# 4GModule-EC25.net
KiCad netlist of a schematic drawn in Altium Designer
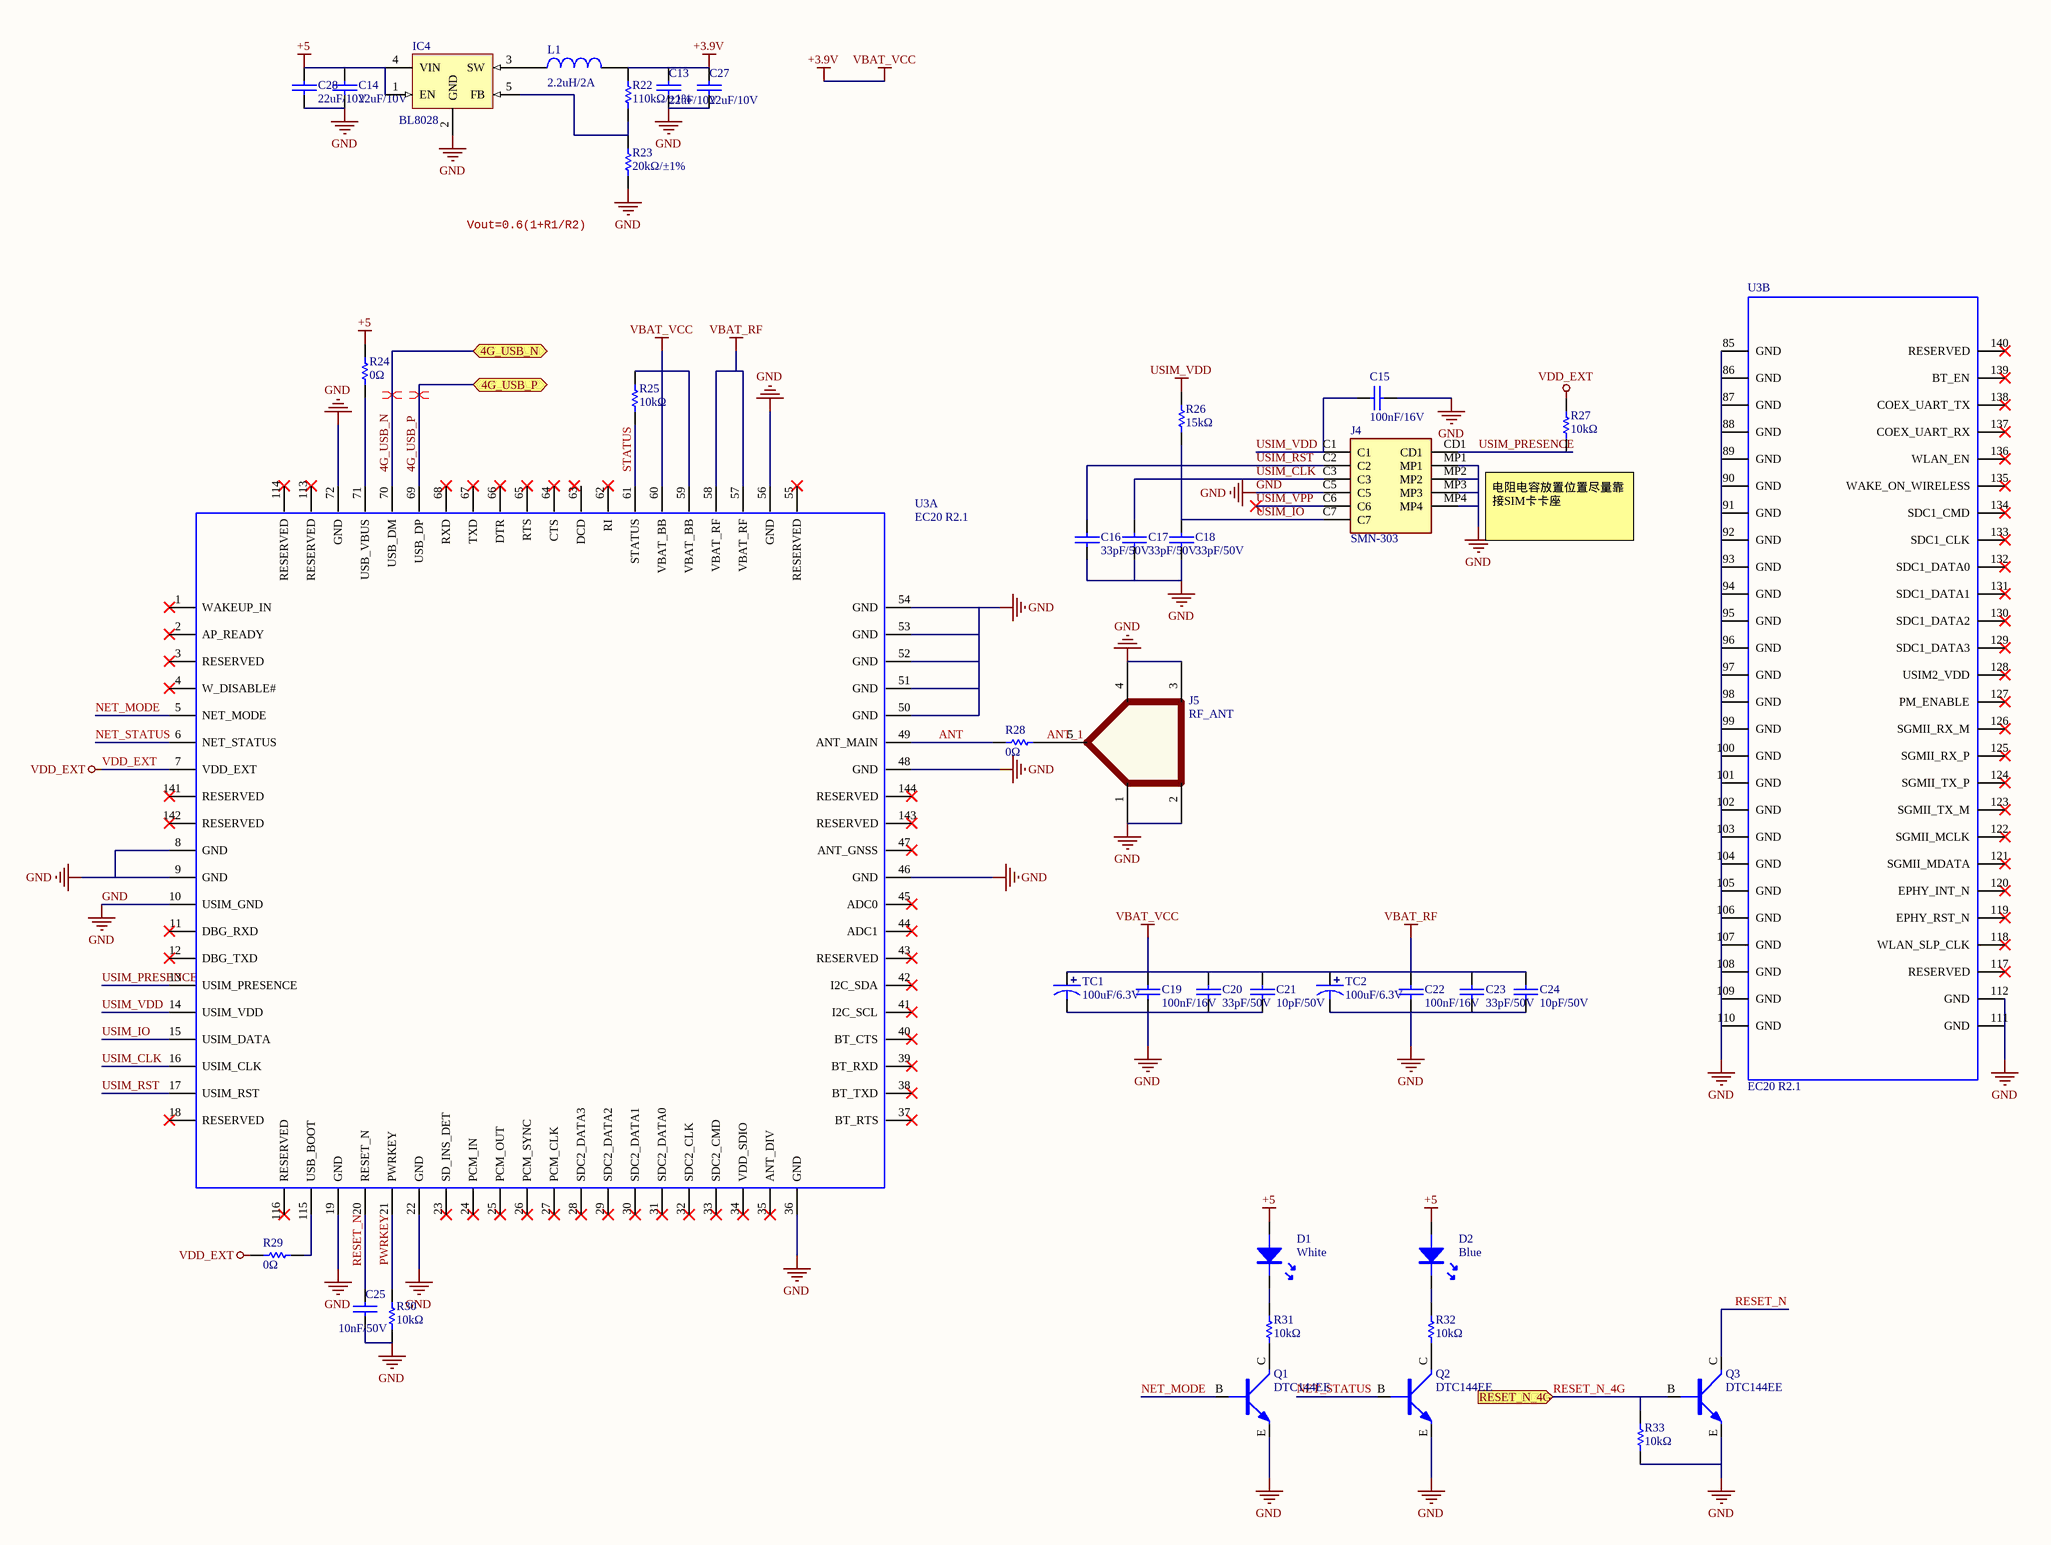
[diagram p0: 4GModule-EC25.SchDoc]

(export (version "E")
  (design (tool "Eeschema 10.0.6"))
  (components
    (comp (ref "C13")
      (value "22uF/10V")
      (footprint "C_0603")
      (description "贴片电容")
      (libsource (lib "IntLib-Passive") (part "Cap_MLCC"))
    )
    (comp (ref "C14")
      (value "22uF/10V")
      (footprint "C_0603")
      (description "贴片电容")
      (libsource (lib "IntLib-Passive") (part "Cap_MLCC"))
    )
    (comp (ref "C15")
      (value "100nF/16V")
      (footprint "C_0402")
      (description "贴片电容")
      (libsource (lib "IntLib-Passive") (part "Cap_MLCC"))
    )
    (comp (ref "C16")
      (value "33pF/50V")
      (footprint "C_0402")
      (description "贴片电容")
      (libsource (lib "IntLib-Passive") (part "Cap_MLCC"))
    )
    (comp (ref "C17")
      (value "33pF/50V")
      (footprint "C_0402")
      (description "贴片电容")
      (libsource (lib "IntLib-Passive") (part "Cap_MLCC"))
    )
    (comp (ref "C18")
      (value "33pF/50V")
      (footprint "C_0402")
      (description "贴片电容")
      (libsource (lib "IntLib-Passive") (part "Cap_MLCC"))
    )
    (comp (ref "C19")
      (value "100nF/16V")
      (footprint "C_0402")
      (description "贴片电容")
      (libsource (lib "IntLib-Passive") (part "Cap_MLCC"))
    )
    (comp (ref "C20")
      (value "33pF/50V")
      (footprint "C_0402")
      (description "贴片电容")
      (libsource (lib "IntLib-Passive") (part "Cap_MLCC"))
    )
    (comp (ref "C21")
      (value "10pF/50V")
      (footprint "C_0402")
      (description "贴片电容")
      (libsource (lib "IntLib-Passive") (part "Cap_MLCC"))
    )
    (comp (ref "C22")
      (value "100nF/16V")
      (footprint "C_0402")
      (description "贴片电容")
      (libsource (lib "IntLib-Passive") (part "Cap_MLCC"))
    )
    (comp (ref "C23")
      (value "33pF/50V")
      (footprint "C_0402")
      (description "贴片电容")
      (libsource (lib "IntLib-Passive") (part "Cap_MLCC"))
    )
    (comp (ref "C24")
      (value "10pF/50V")
      (footprint "C_0402")
      (description "贴片电容")
      (libsource (lib "IntLib-Passive") (part "Cap_MLCC"))
    )
    (comp (ref "C25")
      (value "10nF/50V")
      (footprint "C_0402")
      (description "贴片电容")
      (libsource (lib "IntLib-Passive") (part "Cap_MLCC"))
    )
    (comp (ref "C27")
      (value "22uF/10V")
      (footprint "IntLib-Passive:C_0603")
      (description "贴片电容")
      (libsource (lib "IntLib-Passive") (part "Cap_MLCC"))
    )
    (comp (ref "C28")
      (value "22uF/10V")
      (footprint "IntLib-Passive:C_0603")
      (description "贴片电容")
      (libsource (lib "IntLib-Passive") (part "Cap_MLCC"))
    )
    (comp (ref "D1")
      (value "White")
      (footprint "LED-0603-W")
      (description "贴片LED")
      (libsource (lib "IntLib-Active") (part "LED_SMD"))
    )
    (comp (ref "D2")
      (value "Blue")
      (footprint "LED-0603-B")
      (description "贴片LED")
      (libsource (lib "IntLib-Active") (part "LED_SMD"))
    )
    (comp (ref "IC4")
      (value "BL8028")
      (footprint "SOT23-5")
      (description "DC-DC 芯片")
      (libsource (lib "IntLib-IC") (part "BL8028"))
    )
    (comp (ref "J4")
      (value "SMN-303")
      (footprint "SimCard_SMN-303")
      (description "NANO SIM卡座")
      (libsource (lib "IntLib-Connector") (part "SimCard_Nano"))
    )
    (comp (ref "J5")
      (value "RF_ANT")
      (footprint "RF_MCX")
      (description "RF 天线座")
      (libsource (lib "IntLib-Connector") (part "RF_ANT"))
    )
    (comp (ref "L1")
      (value "2.2uH/2A")
      (footprint "IntLib-Passive:L_1008")
      (description "小功率贴片电感")
      (libsource (lib "Passive-Ind") (part "Ind_SMD"))
    )
    (comp (ref "Q1")
      (value "DTC144EE")
      (footprint "IntLib-Active:SOT-523")
      (description "NPN三极管")
      (libsource (lib "Active-BJT") (part "BJT_NPN"))
    )
    (comp (ref "Q2")
      (value "DTC144EE")
      (footprint "IntLib-Active:SOT-523")
      (description "NPN三极管")
      (libsource (lib "Active-BJT") (part "BJT_NPN"))
    )
    (comp (ref "Q3")
      (value "DTC144EE")
      (footprint "IntLib-Active:SOT-523")
      (description "NPN三极管")
      (libsource (lib "Active-BJT") (part "BJT_NPN"))
    )
    (comp (ref "R22")
      (value "110kΩ/±1%")
      (footprint "R_0402")
      (description "贴片电阻")
      (libsource (lib "IntLib-Passive") (part "Res_SMD"))
    )
    (comp (ref "R23")
      (value "20kΩ/±1%")
      (footprint "R_0402")
      (description "贴片电阻")
      (libsource (lib "IntLib-Passive") (part "Res_SMD"))
    )
    (comp (ref "R24")
      (value "0Ω")
      (footprint "R_0402")
      (description "贴片电阻")
      (libsource (lib "IntLib-Passive") (part "Res_SMD"))
    )
    (comp (ref "R25")
      (value "10kΩ")
      (footprint "R_0402")
      (description "贴片电阻")
      (libsource (lib "IntLib-Passive") (part "Res_SMD"))
    )
    (comp (ref "R26")
      (value "15kΩ")
      (footprint "R_0402")
      (description "贴片电阻")
      (libsource (lib "IntLib-Passive") (part "Res_SMD"))
    )
    (comp (ref "R27")
      (value "10kΩ")
      (footprint "R_0402")
      (description "贴片电阻")
      (libsource (lib "IntLib-Passive") (part "Res_SMD"))
    )
    (comp (ref "R28")
      (value "0Ω")
      (footprint "R_0402")
      (description "贴片电阻")
      (libsource (lib "IntLib-Passive") (part "Res_SMD"))
    )
    (comp (ref "R29")
      (value "0Ω")
      (footprint "R_0402")
      (description "贴片电阻")
      (libsource (lib "IntLib-Passive") (part "Res_SMD"))
    )
    (comp (ref "R30")
      (value "10kΩ")
      (footprint "R_0402")
      (description "贴片电阻")
      (libsource (lib "IntLib-Passive") (part "Res_SMD"))
    )
    (comp (ref "R31")
      (value "10kΩ")
      (footprint "R_0402")
      (description "贴片电阻")
      (libsource (lib "IntLib-Passive") (part "Res_SMD"))
    )
    (comp (ref "R32")
      (value "10kΩ")
      (footprint "R_0402")
      (description "贴片电阻")
      (libsource (lib "IntLib-Passive") (part "Res_SMD"))
    )
    (comp (ref "R33")
      (value "10kΩ")
      (footprint "R_0402")
      (description "贴片电阻")
      (libsource (lib "IntLib-Passive") (part "Res_SMD"))
    )
    (comp (ref "TC1")
      (value "100uF/6.3V")
      (footprint "TAJ-B/3528")
      (description "钽电容")
      (libsource (lib "IntLib-Passive") (part "Cap_TAN"))
    )
    (comp (ref "TC2")
      (value "100uF/6.3V")
      (footprint "TAJ-B/3528")
      (description "钽电容")
      (libsource (lib "IntLib-Passive") (part "Cap_TAN"))
    )
    (comp (ref "U3")
      (value "EC20 R2.1")
      (footprint "IntLib-Module:LCC-144_29.0X32.0X1.3P")
      (description "EC20邮票孔模组")
      (libsource (lib "Module-RF") (part "Module_EC20-R2.1"))
    )
  )
  (nets
    (net (code "1") (name "+3.9V") (class "Default")
      (node (ref "C13") (pin "2") (pinfunction "2_2") (pintype "passive"))
      (node (ref "C19") (pin "2") (pinfunction "2_2") (pintype "passive"))
      (node (ref "C20") (pin "2") (pinfunction "2_2") (pintype "passive"))
      (node (ref "C21") (pin "2") (pinfunction "2_2") (pintype "passive"))
      (node (ref "C22") (pin "2") (pinfunction "2_2") (pintype "passive"))
      (node (ref "C23") (pin "2") (pinfunction "2_2") (pintype "passive"))
      (node (ref "C24") (pin "2") (pinfunction "2_2") (pintype "passive"))
      (node (ref "C27") (pin "2") (pinfunction "2_2") (pintype "passive"))
      (node (ref "L1") (pin "2") (pinfunction "2_2") (pintype "passive"))
      (node (ref "R22") (pin "2") (pinfunction "2_2") (pintype "passive"))
      (node (ref "R25") (pin "2") (pinfunction "2_2") (pintype "passive"))
      (node (ref "TC1") (pin "1") (pinfunction "1_1") (pintype "passive"))
      (node (ref "TC2") (pin "1") (pinfunction "1_1") (pintype "passive"))
      (node (ref "U3") (pin "57") (pinfunction "VBAT_RF_57") (pintype "passive"))
      (node (ref "U3") (pin "58") (pinfunction "VBAT_RF_58") (pintype "passive"))
      (node (ref "U3") (pin "59") (pinfunction "VBAT_BB_59") (pintype "passive"))
      (node (ref "U3") (pin "60") (pinfunction "VBAT_BB_60") (pintype "passive"))
    )
    (net (code "2") (name "+5") (class "Default")
      (node (ref "C14") (pin "2") (pinfunction "2_2") (pintype "passive"))
      (node (ref "C28") (pin "2") (pinfunction "2_2") (pintype "passive"))
      (node (ref "D1") (pin "A") (pinfunction "A_A") (pintype "passive"))
      (node (ref "D2") (pin "A") (pinfunction "A_A") (pintype "passive"))
      (node (ref "IC4") (pin "1") (pinfunction "EN_1") (pintype "input"))
      (node (ref "IC4") (pin "4") (pinfunction "VIN_4") (pintype "power_in"))
      (node (ref "R24") (pin "2") (pinfunction "2_2") (pintype "passive"))
    )
    (net (code "3") (name "/4G_USB_N") (class "Default")
      (node (ref "U3") (pin "70") (pinfunction "USB_DM_70") (pintype "passive"))
    )
    (net (code "4") (name "/4G_USB_P") (class "Default")
      (node (ref "U3") (pin "69") (pinfunction "USB_DP_69") (pintype "passive"))
    )
    (net (code "5") (name "/ANT") (class "Default")
      (node (ref "R28") (pin "1") (pinfunction "1_1") (pintype "passive"))
      (node (ref "U3") (pin "49") (pinfunction "ANT_MAIN_49") (pintype "passive"))
    )
    (net (code "6") (name "/ANT_1") (class "Default")
      (node (ref "J5") (pin "5") (pinfunction "5_5") (pintype "passive"))
      (node (ref "R28") (pin "2") (pinfunction "2_2") (pintype "passive"))
    )
    (net (code "7") (name "/NET_MODE") (class "Default")
      (node (ref "Q1") (pin "B") (pinfunction "B_B") (pintype "passive"))
      (node (ref "U3") (pin "5") (pinfunction "NET_MODE_5") (pintype "passive"))
    )
    (net (code "8") (name "/NET_STATUS") (class "Default")
      (node (ref "Q2") (pin "B") (pinfunction "B_B") (pintype "passive"))
      (node (ref "U3") (pin "6") (pinfunction "NET_STATUS_6") (pintype "passive"))
    )
    (net (code "9") (name "/PWRKEY") (class "Default")
      (node (ref "R30") (pin "2") (pinfunction "2_2") (pintype "passive"))
      (node (ref "U3") (pin "21") (pinfunction "PWRKEY_21") (pintype "passive"))
    )
    (net (code "10") (name "/RESET_N") (class "Default")
      (node (ref "C25") (pin "2") (pinfunction "2_2") (pintype "passive"))
      (node (ref "Q3") (pin "C") (pinfunction "C_C") (pintype "passive"))
      (node (ref "U3") (pin "20") (pinfunction "RESET_N_20") (pintype "passive"))
    )
    (net (code "11") (name "/RESET_N_4G") (class "Default")
      (node (ref "Q3") (pin "B") (pinfunction "B_B") (pintype "passive"))
      (node (ref "R33") (pin "2") (pinfunction "2_2") (pintype "passive"))
    )
    (net (code "12") (name "/STATUS") (class "Default")
      (node (ref "R25") (pin "1") (pinfunction "1_1") (pintype "passive"))
      (node (ref "U3") (pin "61") (pinfunction "STATUS_61") (pintype "passive"))
    )
    (net (code "13") (name "/USIM_CLK") (class "Default")
      (node (ref "C17") (pin "2") (pinfunction "2_2") (pintype "passive"))
      (node (ref "J4") (pin "C3") (pinfunction "C3_C3") (pintype "passive"))
      (node (ref "U3") (pin "16") (pinfunction "USIM_CLK_16") (pintype "passive"))
    )
    (net (code "14") (name "/USIM_IO") (class "Default")
      (node (ref "C18") (pin "2") (pinfunction "2_2") (pintype "passive"))
      (node (ref "J4") (pin "C7") (pinfunction "C7_C7") (pintype "passive"))
      (node (ref "R26") (pin "1") (pinfunction "1_1") (pintype "passive"))
      (node (ref "U3") (pin "15") (pinfunction "USIM_DATA_15") (pintype "passive"))
    )
    (net (code "15") (name "/USIM_PRESENCE") (class "Default")
      (node (ref "J4") (pin "CD1") (pinfunction "CD1_CD1") (pintype "passive"))
      (node (ref "R27") (pin "1") (pinfunction "1_1") (pintype "passive"))
      (node (ref "U3") (pin "13") (pinfunction "USIM_PRESENCE_13") (pintype "passive"))
    )
    (net (code "16") (name "/USIM_RST") (class "Default")
      (node (ref "C16") (pin "2") (pinfunction "2_2") (pintype "passive"))
      (node (ref "J4") (pin "C2") (pinfunction "C2_C2") (pintype "passive"))
      (node (ref "U3") (pin "17") (pinfunction "USIM_RST_17") (pintype "passive"))
    )
    (net (code "17") (name "/USIM_VPP") (class "Default")
      (node (ref "J4") (pin "C6") (pinfunction "C6_C6") (pintype "passive+no_connect"))
    )
    (net (code "18") (name "GND") (class "Default")
      (node (ref "C13") (pin "1") (pinfunction "1_1") (pintype "passive"))
      (node (ref "C14") (pin "1") (pinfunction "1_1") (pintype "passive"))
      (node (ref "C15") (pin "1") (pinfunction "1_1") (pintype "passive"))
      (node (ref "C16") (pin "1") (pinfunction "1_1") (pintype "passive"))
      (node (ref "C17") (pin "1") (pinfunction "1_1") (pintype "passive"))
      (node (ref "C18") (pin "1") (pinfunction "1_1") (pintype "passive"))
      (node (ref "C19") (pin "1") (pinfunction "1_1") (pintype "passive"))
      (node (ref "C20") (pin "1") (pinfunction "1_1") (pintype "passive"))
      (node (ref "C21") (pin "1") (pinfunction "1_1") (pintype "passive"))
      (node (ref "C22") (pin "1") (pinfunction "1_1") (pintype "passive"))
      (node (ref "C23") (pin "1") (pinfunction "1_1") (pintype "passive"))
      (node (ref "C24") (pin "1") (pinfunction "1_1") (pintype "passive"))
      (node (ref "C25") (pin "1") (pinfunction "1_1") (pintype "passive"))
      (node (ref "C27") (pin "1") (pinfunction "1_1") (pintype "passive"))
      (node (ref "C28") (pin "1") (pinfunction "1_1") (pintype "passive"))
      (node (ref "IC4") (pin "2") (pinfunction "GND_2") (pintype "power_in"))
      (node (ref "J4") (pin "C5") (pinfunction "C5_C5") (pintype "passive"))
      (node (ref "J4") (pin "MP1") (pinfunction "MP1_MP1") (pintype "passive"))
      (node (ref "J4") (pin "MP2") (pinfunction "MP2_MP2") (pintype "passive"))
      (node (ref "J4") (pin "MP3") (pinfunction "MP3_MP3") (pintype "passive"))
      (node (ref "J4") (pin "MP4") (pinfunction "MP4_MP4") (pintype "passive"))
      (node (ref "J5") (pin "1") (pinfunction "1_1") (pintype "passive"))
      (node (ref "J5") (pin "2") (pinfunction "2_2") (pintype "passive"))
      (node (ref "J5") (pin "3") (pinfunction "3_3") (pintype "passive"))
      (node (ref "J5") (pin "4") (pinfunction "4_4") (pintype "passive"))
      (node (ref "Q1") (pin "E") (pinfunction "E_E") (pintype "passive"))
      (node (ref "Q2") (pin "E") (pinfunction "E_E") (pintype "passive"))
      (node (ref "Q3") (pin "E") (pinfunction "E_E") (pintype "passive"))
      (node (ref "R23") (pin "1") (pinfunction "1_1") (pintype "passive"))
      (node (ref "R30") (pin "1") (pinfunction "1_1") (pintype "passive"))
      (node (ref "R33") (pin "1") (pinfunction "1_1") (pintype "passive"))
      (node (ref "TC1") (pin "2") (pinfunction "2_2") (pintype "passive"))
      (node (ref "TC2") (pin "2") (pinfunction "2_2") (pintype "passive"))
      (node (ref "U3") (pin "10") (pinfunction "USIM_GND_10") (pintype "passive"))
      (node (ref "U3") (pin "100") (pinfunction "GND_100") (pintype "passive"))
      (node (ref "U3") (pin "101") (pinfunction "GND_101") (pintype "passive"))
      (node (ref "U3") (pin "102") (pinfunction "GND_102") (pintype "passive"))
      (node (ref "U3") (pin "103") (pinfunction "GND_103") (pintype "passive"))
      (node (ref "U3") (pin "104") (pinfunction "GND_104") (pintype "passive"))
      (node (ref "U3") (pin "105") (pinfunction "GND_105") (pintype "passive"))
      (node (ref "U3") (pin "106") (pinfunction "GND_106") (pintype "passive"))
      (node (ref "U3") (pin "107") (pinfunction "GND_107") (pintype "passive"))
      (node (ref "U3") (pin "108") (pinfunction "GND_108") (pintype "passive"))
      (node (ref "U3") (pin "109") (pinfunction "GND_109") (pintype "passive"))
      (node (ref "U3") (pin "110") (pinfunction "GND_110") (pintype "passive"))
      (node (ref "U3") (pin "111") (pinfunction "GND_111") (pintype "passive"))
      (node (ref "U3") (pin "112") (pinfunction "GND_112") (pintype "passive"))
      (node (ref "U3") (pin "19") (pinfunction "GND_19") (pintype "passive"))
      (node (ref "U3") (pin "22") (pinfunction "GND_22") (pintype "passive"))
      (node (ref "U3") (pin "36") (pinfunction "GND_36") (pintype "passive"))
      (node (ref "U3") (pin "46") (pinfunction "GND_46") (pintype "passive"))
      (node (ref "U3") (pin "48") (pinfunction "GND_48") (pintype "passive"))
      (node (ref "U3") (pin "50") (pinfunction "GND_50") (pintype "passive"))
      (node (ref "U3") (pin "51") (pinfunction "GND_51") (pintype "passive"))
      (node (ref "U3") (pin "52") (pinfunction "GND_52") (pintype "passive"))
      (node (ref "U3") (pin "53") (pinfunction "GND_53") (pintype "passive"))
      (node (ref "U3") (pin "54") (pinfunction "GND_54") (pintype "passive"))
      (node (ref "U3") (pin "56") (pinfunction "GND_56") (pintype "passive"))
      (node (ref "U3") (pin "72") (pinfunction "GND_72") (pintype "passive"))
      (node (ref "U3") (pin "8") (pinfunction "GND_8") (pintype "passive"))
      (node (ref "U3") (pin "85") (pinfunction "GND_85") (pintype "passive"))
      (node (ref "U3") (pin "86") (pinfunction "GND_86") (pintype "passive"))
      (node (ref "U3") (pin "87") (pinfunction "GND_87") (pintype "passive"))
      (node (ref "U3") (pin "88") (pinfunction "GND_88") (pintype "passive"))
      (node (ref "U3") (pin "89") (pinfunction "GND_89") (pintype "passive"))
      (node (ref "U3") (pin "9") (pinfunction "GND_9") (pintype "passive"))
      (node (ref "U3") (pin "90") (pinfunction "GND_90") (pintype "passive"))
      (node (ref "U3") (pin "91") (pinfunction "GND_91") (pintype "passive"))
      (node (ref "U3") (pin "92") (pinfunction "GND_92") (pintype "passive"))
      (node (ref "U3") (pin "93") (pinfunction "GND_93") (pintype "passive"))
      (node (ref "U3") (pin "94") (pinfunction "GND_94") (pintype "passive"))
      (node (ref "U3") (pin "95") (pinfunction "GND_95") (pintype "passive"))
      (node (ref "U3") (pin "96") (pinfunction "GND_96") (pintype "passive"))
      (node (ref "U3") (pin "97") (pinfunction "GND_97") (pintype "passive"))
      (node (ref "U3") (pin "98") (pinfunction "GND_98") (pintype "passive"))
      (node (ref "U3") (pin "99") (pinfunction "GND_99") (pintype "passive"))
    )
    (net (code "19") (name "Net-(D1-PadK)") (class "Default")
      (node (ref "D1") (pin "K") (pinfunction "K_K") (pintype "passive"))
      (node (ref "R31") (pin "2") (pinfunction "2_2") (pintype "passive"))
    )
    (net (code "20") (name "Net-(D2-PadK)") (class "Default")
      (node (ref "D2") (pin "K") (pinfunction "K_K") (pintype "passive"))
      (node (ref "R32") (pin "2") (pinfunction "2_2") (pintype "passive"))
    )
    (net (code "21") (name "Net-(IC4-FB)") (class "Default")
      (node (ref "IC4") (pin "5") (pinfunction "FB_5") (pintype "input"))
      (node (ref "R22") (pin "1") (pinfunction "1_1") (pintype "passive"))
      (node (ref "R23") (pin "2") (pinfunction "2_2") (pintype "passive"))
    )
    (net (code "22") (name "Net-(IC4-SW)") (class "Default")
      (node (ref "IC4") (pin "3") (pinfunction "SW_3") (pintype "input"))
      (node (ref "L1") (pin "1") (pinfunction "1_1") (pintype "passive"))
    )
    (net (code "23") (name "Net-(Q1-PadC)") (class "Default")
      (node (ref "Q1") (pin "C") (pinfunction "C_C") (pintype "passive"))
      (node (ref "R31") (pin "1") (pinfunction "1_1") (pintype "passive"))
    )
    (net (code "24") (name "Net-(Q2-PadC)") (class "Default")
      (node (ref "Q2") (pin "C") (pinfunction "C_C") (pintype "passive"))
      (node (ref "R32") (pin "1") (pinfunction "1_1") (pintype "passive"))
    )
    (net (code "25") (name "Net-(U3A-USB_BOOT)") (class "Default")
      (node (ref "R29") (pin "1") (pinfunction "1_1") (pintype "passive"))
      (node (ref "U3") (pin "115") (pinfunction "USB_BOOT_115") (pintype "passive"))
    )
    (net (code "26") (name "Net-(U3A-USB_VBUS)") (class "Default")
      (node (ref "R24") (pin "1") (pinfunction "1_1") (pintype "passive"))
      (node (ref "U3") (pin "71") (pinfunction "USB_VBUS_71") (pintype "passive"))
    )
    (net (code "27") (name "USIM_VDD") (class "Default")
      (node (ref "C15") (pin "2") (pinfunction "2_2") (pintype "passive"))
      (node (ref "J4") (pin "C1") (pinfunction "C1_C1") (pintype "passive"))
      (node (ref "R26") (pin "2") (pinfunction "2_2") (pintype "passive"))
      (node (ref "U3") (pin "14") (pinfunction "USIM_VDD_14") (pintype "passive"))
    )
    (net (code "28") (name "VDD_EXT") (class "Default")
      (node (ref "R27") (pin "2") (pinfunction "2_2") (pintype "passive"))
      (node (ref "R29") (pin "2") (pinfunction "2_2") (pintype "passive"))
      (node (ref "U3") (pin "7") (pinfunction "VDD_EXT_7") (pintype "passive"))
    )
    (net (code "29") (name "unconnected-(U3A-ADC0-Pad45)") (class "Default")
      (node (ref "U3") (pin "45") (pinfunction "ADC0_45") (pintype "passive+no_connect"))
    )
    (net (code "30") (name "unconnected-(U3A-ADC1-Pad44)") (class "Default")
      (node (ref "U3") (pin "44") (pinfunction "ADC1_44") (pintype "passive+no_connect"))
    )
    (net (code "31") (name "unconnected-(U3A-ANT_DIV-Pad35)") (class "Default")
      (node (ref "U3") (pin "35") (pinfunction "ANT_DIV_35") (pintype "passive+no_connect"))
    )
    (net (code "32") (name "unconnected-(U3A-ANT_GNSS-Pad47)") (class "Default")
      (node (ref "U3") (pin "47") (pinfunction "ANT_GNSS_47") (pintype "passive+no_connect"))
    )
    (net (code "33") (name "unconnected-(U3A-AP_READY-Pad2)") (class "Default")
      (node (ref "U3") (pin "2") (pinfunction "AP_READY_2") (pintype "passive+no_connect"))
    )
    (net (code "34") (name "unconnected-(U3A-BT_CTS-Pad40)") (class "Default")
      (node (ref "U3") (pin "40") (pinfunction "BT_CTS_40") (pintype "passive+no_connect"))
    )
    (net (code "35") (name "unconnected-(U3A-BT_RTS-Pad37)") (class "Default")
      (node (ref "U3") (pin "37") (pinfunction "BT_RTS_37") (pintype "passive+no_connect"))
    )
    (net (code "36") (name "unconnected-(U3A-BT_RXD-Pad39)") (class "Default")
      (node (ref "U3") (pin "39") (pinfunction "BT_RXD_39") (pintype "passive+no_connect"))
    )
    (net (code "37") (name "unconnected-(U3A-BT_TXD-Pad38)") (class "Default")
      (node (ref "U3") (pin "38") (pinfunction "BT_TXD_38") (pintype "passive+no_connect"))
    )
    (net (code "38") (name "unconnected-(U3A-CTS-Pad64)") (class "Default")
      (node (ref "U3") (pin "64") (pinfunction "CTS_64") (pintype "passive+no_connect"))
    )
    (net (code "39") (name "unconnected-(U3A-DBG_RXD-Pad11)") (class "Default")
      (node (ref "U3") (pin "11") (pinfunction "DBG_RXD_11") (pintype "passive+no_connect"))
    )
    (net (code "40") (name "unconnected-(U3A-DBG_TXD-Pad12)") (class "Default")
      (node (ref "U3") (pin "12") (pinfunction "DBG_TXD_12") (pintype "passive+no_connect"))
    )
    (net (code "41") (name "unconnected-(U3A-DCD-Pad63)") (class "Default")
      (node (ref "U3") (pin "63") (pinfunction "DCD_63") (pintype "passive"))
    )
    (net (code "42") (name "unconnected-(U3A-DTR-Pad66)") (class "Default")
      (node (ref "U3") (pin "66") (pinfunction "DTR_66") (pintype "passive+no_connect"))
    )
    (net (code "43") (name "unconnected-(U3A-I2C_SCL-Pad41)") (class "Default")
      (node (ref "U3") (pin "41") (pinfunction "I2C_SCL_41") (pintype "passive+no_connect"))
    )
    (net (code "44") (name "unconnected-(U3A-I2C_SDA-Pad42)") (class "Default")
      (node (ref "U3") (pin "42") (pinfunction "I2C_SDA_42") (pintype "passive+no_connect"))
    )
    (net (code "45") (name "unconnected-(U3A-PCM_CLK-Pad27)") (class "Default")
      (node (ref "U3") (pin "27") (pinfunction "PCM_CLK_27") (pintype "passive+no_connect"))
    )
    (net (code "46") (name "unconnected-(U3A-PCM_IN-Pad24)") (class "Default")
      (node (ref "U3") (pin "24") (pinfunction "PCM_IN_24") (pintype "passive+no_connect"))
    )
    (net (code "47") (name "unconnected-(U3A-PCM_OUT-Pad25)") (class "Default")
      (node (ref "U3") (pin "25") (pinfunction "PCM_OUT_25") (pintype "passive+no_connect"))
    )
    (net (code "48") (name "unconnected-(U3A-PCM_SYNC-Pad26)") (class "Default")
      (node (ref "U3") (pin "26") (pinfunction "PCM_SYNC_26") (pintype "passive+no_connect"))
    )
    (net (code "49") (name "unconnected-(U3A-RESERVED-Pad3)") (class "Default")
      (node (ref "U3") (pin "3") (pinfunction "RESERVED_3") (pintype "passive+no_connect"))
    )
    (net (code "50") (name "unconnected-(U3A-RESERVED-Pad18)") (class "Default")
      (node (ref "U3") (pin "18") (pinfunction "RESERVED_18") (pintype "passive+no_connect"))
    )
    (net (code "51") (name "unconnected-(U3A-RESERVED-Pad43)") (class "Default")
      (node (ref "U3") (pin "43") (pinfunction "RESERVED_43") (pintype "passive+no_connect"))
    )
    (net (code "52") (name "unconnected-(U3A-RESERVED-Pad55)") (class "Default")
      (node (ref "U3") (pin "55") (pinfunction "RESERVED_55") (pintype "passive+no_connect"))
    )
    (net (code "53") (name "unconnected-(U3A-RESERVED-Pad113)") (class "Default")
      (node (ref "U3") (pin "113") (pinfunction "RESERVED_113") (pintype "passive+no_connect"))
    )
    (net (code "54") (name "unconnected-(U3A-RESERVED-Pad114)") (class "Default")
      (node (ref "U3") (pin "114") (pinfunction "RESERVED_114") (pintype "passive+no_connect"))
    )
    (net (code "55") (name "unconnected-(U3A-RESERVED-Pad116)") (class "Default")
      (node (ref "U3") (pin "116") (pinfunction "RESERVED_116") (pintype "passive+no_connect"))
    )
    (net (code "56") (name "unconnected-(U3A-RESERVED-Pad141)") (class "Default")
      (node (ref "U3") (pin "141") (pinfunction "RESERVED_141") (pintype "passive+no_connect"))
    )
    (net (code "57") (name "unconnected-(U3A-RESERVED-Pad142)") (class "Default")
      (node (ref "U3") (pin "142") (pinfunction "RESERVED_142") (pintype "passive+no_connect"))
    )
    (net (code "58") (name "unconnected-(U3A-RESERVED-Pad143)") (class "Default")
      (node (ref "U3") (pin "143") (pinfunction "RESERVED_143") (pintype "passive+no_connect"))
    )
    (net (code "59") (name "unconnected-(U3A-RESERVED-Pad144)") (class "Default")
      (node (ref "U3") (pin "144") (pinfunction "RESERVED_144") (pintype "passive+no_connect"))
    )
    (net (code "60") (name "unconnected-(U3A-RI-Pad62)") (class "Default")
      (node (ref "U3") (pin "62") (pinfunction "RI_62") (pintype "passive+no_connect"))
    )
    (net (code "61") (name "unconnected-(U3A-RTS-Pad65)") (class "Default")
      (node (ref "U3") (pin "65") (pinfunction "RTS_65") (pintype "passive+no_connect"))
    )
    (net (code "62") (name "unconnected-(U3A-RXD-Pad68)") (class "Default")
      (node (ref "U3") (pin "68") (pinfunction "RXD_68") (pintype "passive+no_connect"))
    )
    (net (code "63") (name "unconnected-(U3A-SDC2_CLK-Pad32)") (class "Default")
      (node (ref "U3") (pin "32") (pinfunction "SDC2_CLK_32") (pintype "passive+no_connect"))
    )
    (net (code "64") (name "unconnected-(U3A-SDC2_CMD-Pad33)") (class "Default")
      (node (ref "U3") (pin "33") (pinfunction "SDC2_CMD_33") (pintype "passive+no_connect"))
    )
    (net (code "65") (name "unconnected-(U3A-SDC2_DATA0-Pad31)") (class "Default")
      (node (ref "U3") (pin "31") (pinfunction "SDC2_DATA0_31") (pintype "passive+no_connect"))
    )
    (net (code "66") (name "unconnected-(U3A-SDC2_DATA1-Pad30)") (class "Default")
      (node (ref "U3") (pin "30") (pinfunction "SDC2_DATA1_30") (pintype "passive+no_connect"))
    )
    (net (code "67") (name "unconnected-(U3A-SDC2_DATA2-Pad29)") (class "Default")
      (node (ref "U3") (pin "29") (pinfunction "SDC2_DATA2_29") (pintype "passive+no_connect"))
    )
    (net (code "68") (name "unconnected-(U3A-SDC2_DATA3-Pad28)") (class "Default")
      (node (ref "U3") (pin "28") (pinfunction "SDC2_DATA3_28") (pintype "passive+no_connect"))
    )
    (net (code "69") (name "unconnected-(U3A-SD_INS_DET-Pad23)") (class "Default")
      (node (ref "U3") (pin "23") (pinfunction "SD_INS_DET_23") (pintype "passive+no_connect"))
    )
    (net (code "70") (name "unconnected-(U3A-TXD-Pad67)") (class "Default")
      (node (ref "U3") (pin "67") (pinfunction "TXD_67") (pintype "passive+no_connect"))
    )
    (net (code "71") (name "unconnected-(U3A-VDD_SDIO-Pad34)") (class "Default")
      (node (ref "U3") (pin "34") (pinfunction "VDD_SDIO_34") (pintype "passive+no_connect"))
    )
    (net (code "72") (name "unconnected-(U3A-WAKEUP_IN-Pad1)") (class "Default")
      (node (ref "U3") (pin "1") (pinfunction "WAKEUP_IN_1") (pintype "passive+no_connect"))
    )
    (net (code "73") (name "unconnected-(U3A-W_DISABLE#-Pad4)") (class "Default")
      (node (ref "U3") (pin "4") (pinfunction "W_DISABLE#_4") (pintype "passive+no_connect"))
    )
    (net (code "74") (name "unconnected-(U3B-BT_EN-Pad139)") (class "Default")
      (node (ref "U3") (pin "139") (pinfunction "BT_EN_139") (pintype "passive+no_connect"))
    )
    (net (code "75") (name "unconnected-(U3B-COEX_UART_RX-Pad137)") (class "Default")
      (node (ref "U3") (pin "137") (pinfunction "COEX_UART_RX_137") (pintype "passive+no_connect"))
    )
    (net (code "76") (name "unconnected-(U3B-COEX_UART_TX-Pad138)") (class "Default")
      (node (ref "U3") (pin "138") (pinfunction "COEX_UART_TX_138") (pintype "passive+no_connect"))
    )
    (net (code "77") (name "unconnected-(U3B-EPHY_INT_N-Pad120)") (class "Default")
      (node (ref "U3") (pin "120") (pinfunction "EPHY_INT_N_120") (pintype "passive+no_connect"))
    )
    (net (code "78") (name "unconnected-(U3B-EPHY_RST_N-Pad119)") (class "Default")
      (node (ref "U3") (pin "119") (pinfunction "EPHY_RST_N_119") (pintype "passive+no_connect"))
    )
    (net (code "79") (name "unconnected-(U3B-PM_ENABLE-Pad127)") (class "Default")
      (node (ref "U3") (pin "127") (pinfunction "PM_ENABLE_127") (pintype "passive+no_connect"))
    )
    (net (code "80") (name "unconnected-(U3B-RESERVED-Pad117)") (class "Default")
      (node (ref "U3") (pin "117") (pinfunction "RESERVED_117") (pintype "passive+no_connect"))
    )
    (net (code "81") (name "unconnected-(U3B-RESERVED-Pad140)") (class "Default")
      (node (ref "U3") (pin "140") (pinfunction "RESERVED_140") (pintype "passive+no_connect"))
    )
    (net (code "82") (name "unconnected-(U3B-SDC1_CLK-Pad133)") (class "Default")
      (node (ref "U3") (pin "133") (pinfunction "SDC1_CLK_133") (pintype "passive+no_connect"))
    )
    (net (code "83") (name "unconnected-(U3B-SDC1_CMD-Pad134)") (class "Default")
      (node (ref "U3") (pin "134") (pinfunction "SDC1_CMD_134") (pintype "passive+no_connect"))
    )
    (net (code "84") (name "unconnected-(U3B-SDC1_DATA0-Pad132)") (class "Default")
      (node (ref "U3") (pin "132") (pinfunction "SDC1_DATA0_132") (pintype "passive+no_connect"))
    )
    (net (code "85") (name "unconnected-(U3B-SDC1_DATA1-Pad131)") (class "Default")
      (node (ref "U3") (pin "131") (pinfunction "SDC1_DATA1_131") (pintype "passive+no_connect"))
    )
    (net (code "86") (name "unconnected-(U3B-SDC1_DATA2-Pad130)") (class "Default")
      (node (ref "U3") (pin "130") (pinfunction "SDC1_DATA2_130") (pintype "passive+no_connect"))
    )
    (net (code "87") (name "unconnected-(U3B-SDC1_DATA3-Pad129)") (class "Default")
      (node (ref "U3") (pin "129") (pinfunction "SDC1_DATA3_129") (pintype "passive+no_connect"))
    )
    (net (code "88") (name "unconnected-(U3B-SGMII_MCLK-Pad122)") (class "Default")
      (node (ref "U3") (pin "122") (pinfunction "SGMII_MCLK_122") (pintype "passive+no_connect"))
    )
    (net (code "89") (name "unconnected-(U3B-SGMII_MDATA-Pad121)") (class "Default")
      (node (ref "U3") (pin "121") (pinfunction "SGMII_MDATA_121") (pintype "passive+no_connect"))
    )
    (net (code "90") (name "unconnected-(U3B-SGMII_RX_M-Pad126)") (class "Default")
      (node (ref "U3") (pin "126") (pinfunction "SGMII_RX_M_126") (pintype "passive+no_connect"))
    )
    (net (code "91") (name "unconnected-(U3B-SGMII_RX_P-Pad125)") (class "Default")
      (node (ref "U3") (pin "125") (pinfunction "SGMII_RX_P_125") (pintype "passive+no_connect"))
    )
    (net (code "92") (name "unconnected-(U3B-SGMII_TX_M-Pad123)") (class "Default")
      (node (ref "U3") (pin "123") (pinfunction "SGMII_TX_M_123") (pintype "passive+no_connect"))
    )
    (net (code "93") (name "unconnected-(U3B-SGMII_TX_P-Pad124)") (class "Default")
      (node (ref "U3") (pin "124") (pinfunction "SGMII_TX_P_124") (pintype "passive+no_connect"))
    )
    (net (code "94") (name "unconnected-(U3B-USIM2_VDD-Pad128)") (class "Default")
      (node (ref "U3") (pin "128") (pinfunction "USIM2_VDD_128") (pintype "passive+no_connect"))
    )
    (net (code "95") (name "unconnected-(U3B-WAKE_ON_WIRELESS-Pad135)") (class "Default")
      (node (ref "U3") (pin "135") (pinfunction "WAKE_ON_WIRELESS_135") (pintype "passive+no_connect"))
    )
    (net (code "96") (name "unconnected-(U3B-WLAN_EN-Pad136)") (class "Default")
      (node (ref "U3") (pin "136") (pinfunction "WLAN_EN_136") (pintype "passive+no_connect"))
    )
    (net (code "97") (name "unconnected-(U3B-WLAN_SLP_CLK-Pad118)") (class "Default")
      (node (ref "U3") (pin "118") (pinfunction "WLAN_SLP_CLK_118") (pintype "passive+no_connect"))
    )
  )
)
